# schaltplan_v2.net
KiCad netlist of a schematic drawn in EAGLE
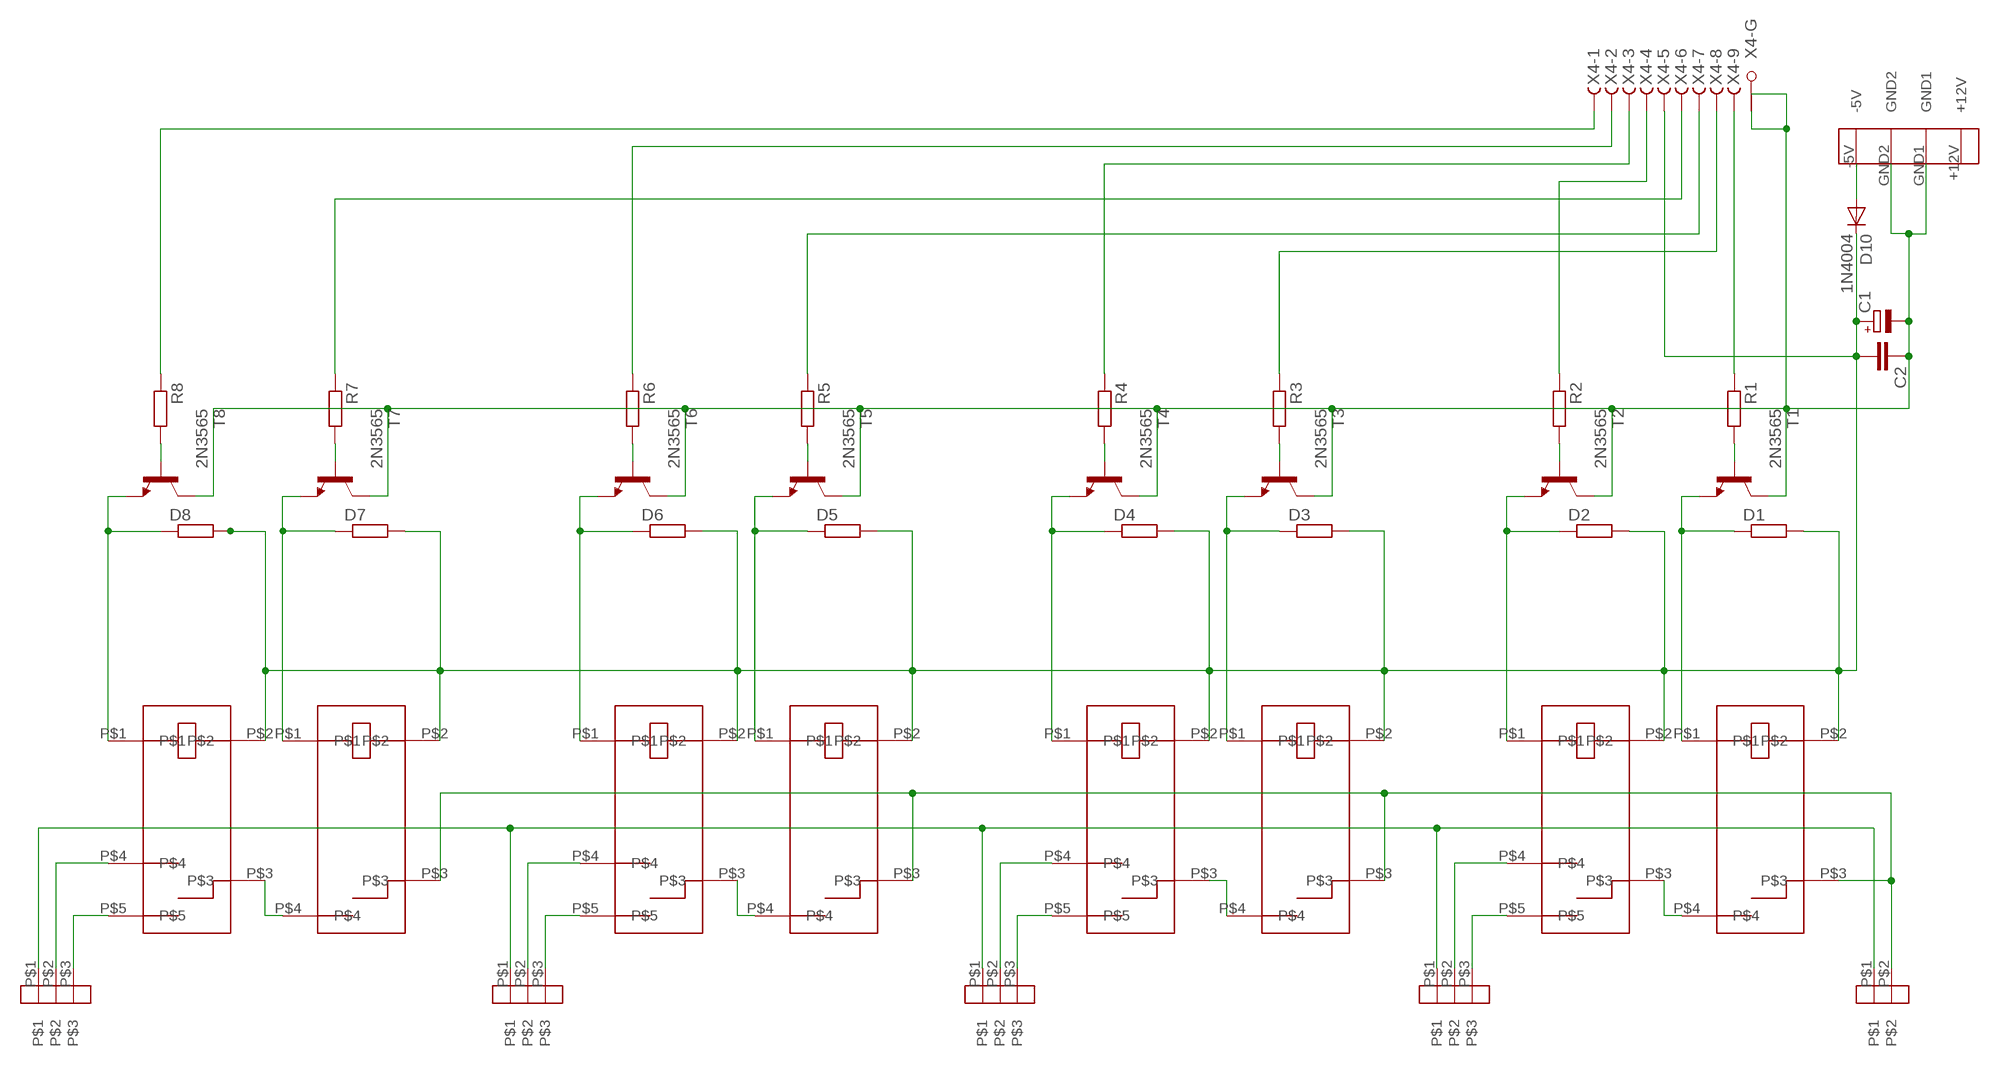
[diagram p0: schematic, sheet 1]

(export (version "E")
  (design (tool "Eeschema 10.0.6"))
  (components
    (comp (ref "C1")
      (value "CPOL-EUE3.5-8")
      (footprint "eagle-import:E3,5-8")
      (libsource (lib "eagle-import") (part "CPOL-EUE3.5-8"))
    )
    (comp (ref "C2")
      (value "C-EU025-030X050")
      (footprint "eagle-import:C025-030X050")
      (libsource (lib "eagle-import") (part "C-EU025-030X050"))
    )
    (comp (ref "D1")
      (value "R-EU_0207/2V")
      (footprint "eagle-import:0207_2V")
      (libsource (lib "eagle-import") (part "R-EU_0207/2V"))
    )
    (comp (ref "D2")
      (value "R-EU_0207/2V")
      (footprint "eagle-import:0207_2V")
      (libsource (lib "eagle-import") (part "R-EU_0207/2V"))
    )
    (comp (ref "D3")
      (value "R-EU_0207/2V")
      (footprint "eagle-import:0207_2V")
      (libsource (lib "eagle-import") (part "R-EU_0207/2V"))
    )
    (comp (ref "D4")
      (value "R-EU_0207/2V")
      (footprint "eagle-import:0207_2V")
      (libsource (lib "eagle-import") (part "R-EU_0207/2V"))
    )
    (comp (ref "D5")
      (value "R-EU_0207/2V")
      (footprint "eagle-import:0207_2V")
      (libsource (lib "eagle-import") (part "R-EU_0207/2V"))
    )
    (comp (ref "D6")
      (value "R-EU_0207/2V")
      (footprint "eagle-import:0207_2V")
      (libsource (lib "eagle-import") (part "R-EU_0207/2V"))
    )
    (comp (ref "D7")
      (value "R-EU_0207/2V")
      (footprint "eagle-import:0207_2V")
      (libsource (lib "eagle-import") (part "R-EU_0207/2V"))
    )
    (comp (ref "D8")
      (value "R-EU_0207/2V")
      (footprint "eagle-import:0207_2V")
      (libsource (lib "eagle-import") (part "R-EU_0207/2V"))
    )
    (comp (ref "D10")
      (value "1N4004")
      (footprint "eagle-import:DO41-10")
      (libsource (lib "eagle-import") (part "1N4004"))
    )
    (comp (ref "R1")
      (value "R-EU_0207/7")
      (footprint "eagle-import:0207_7")
      (libsource (lib "eagle-import") (part "R-EU_0207/7"))
    )
    (comp (ref "R2")
      (value "R-EU_0207/7")
      (footprint "eagle-import:0207_7")
      (libsource (lib "eagle-import") (part "R-EU_0207/7"))
    )
    (comp (ref "R3")
      (value "R-EU_0207/7")
      (footprint "eagle-import:0207_7")
      (libsource (lib "eagle-import") (part "R-EU_0207/7"))
    )
    (comp (ref "R4")
      (value "R-EU_0207/7")
      (footprint "eagle-import:0207_7")
      (libsource (lib "eagle-import") (part "R-EU_0207/7"))
    )
    (comp (ref "R5")
      (value "R-EU_0207/7")
      (footprint "eagle-import:0207_7")
      (libsource (lib "eagle-import") (part "R-EU_0207/7"))
    )
    (comp (ref "R6")
      (value "R-EU_0207/7")
      (footprint "eagle-import:0207_7")
      (libsource (lib "eagle-import") (part "R-EU_0207/7"))
    )
    (comp (ref "R7")
      (value "R-EU_0207/7")
      (footprint "eagle-import:0207_7")
      (libsource (lib "eagle-import") (part "R-EU_0207/7"))
    )
    (comp (ref "R8")
      (value "R-EU_0207/7")
      (footprint "eagle-import:0207_7")
      (libsource (lib "eagle-import") (part "R-EU_0207/7"))
    )
    (comp (ref "T1")
      (value "2N3565")
      (footprint "eagle-import:TO92")
      (libsource (lib "eagle-import") (part "2N3565"))
    )
    (comp (ref "T2")
      (value "2N3565")
      (footprint "eagle-import:TO92")
      (libsource (lib "eagle-import") (part "2N3565"))
    )
    (comp (ref "T3")
      (value "2N3565")
      (footprint "eagle-import:TO92")
      (libsource (lib "eagle-import") (part "2N3565"))
    )
    (comp (ref "T4")
      (value "2N3565")
      (footprint "eagle-import:TO92")
      (libsource (lib "eagle-import") (part "2N3565"))
    )
    (comp (ref "T5")
      (value "2N3565")
      (footprint "eagle-import:TO92")
      (libsource (lib "eagle-import") (part "2N3565"))
    )
    (comp (ref "T6")
      (value "2N3565")
      (footprint "eagle-import:TO92")
      (libsource (lib "eagle-import") (part "2N3565"))
    )
    (comp (ref "T7")
      (value "2N3565")
      (footprint "eagle-import:TO92")
      (libsource (lib "eagle-import") (part "2N3565"))
    )
    (comp (ref "T8")
      (value "2N3565")
      (footprint "eagle-import:TO92")
      (libsource (lib "eagle-import") (part "2N3565"))
    )
    (comp (ref "U$1")
      (value "JS_05_MN_KT")
      (footprint "eagle-import:JS_05_MN_KT")
      (libsource (lib "eagle-import") (part "JS_05_MN_KT"))
    )
    (comp (ref "U$2")
      (value "JS_05_N_K")
      (footprint "eagle-import:JS_05_N_K")
      (libsource (lib "eagle-import") (part "JS_05_N_K"))
    )
    (comp (ref "U$3")
      (value "JS_05_MN_KT")
      (footprint "eagle-import:JS_05_MN_KT")
      (libsource (lib "eagle-import") (part "JS_05_MN_KT"))
    )
    (comp (ref "U$4")
      (value "JS_05_N_K")
      (footprint "eagle-import:JS_05_N_K")
      (libsource (lib "eagle-import") (part "JS_05_N_K"))
    )
    (comp (ref "U$5")
      (value "JS_05_MN_KT")
      (footprint "eagle-import:JS_05_MN_KT")
      (libsource (lib "eagle-import") (part "JS_05_MN_KT"))
    )
    (comp (ref "U$6")
      (value "JS_05_N_K")
      (footprint "eagle-import:JS_05_N_K")
      (libsource (lib "eagle-import") (part "JS_05_N_K"))
    )
    (comp (ref "U$7")
      (value "JS_05_MN_KT")
      (footprint "eagle-import:JS_05_MN_KT")
      (libsource (lib "eagle-import") (part "JS_05_MN_KT"))
    )
    (comp (ref "U$8")
      (value "JS_05_N_K")
      (footprint "eagle-import:JS_05_N_K")
      (libsource (lib "eagle-import") (part "JS_05_N_K"))
    )
    (comp (ref "U$9")
      (value "WAGO_734_262")
      (footprint "eagle-import:WAGO_734_262")
      (libsource (lib "eagle-import") (part "WAGO_734_262"))
    )
    (comp (ref "U$10")
      (value "WAGO_734_263")
      (footprint "eagle-import:WAGO_734_263")
      (libsource (lib "eagle-import") (part "WAGO_734_263"))
    )
    (comp (ref "U$11")
      (value "WAGO_734_263")
      (footprint "eagle-import:WAGO_734_263")
      (libsource (lib "eagle-import") (part "WAGO_734_263"))
    )
    (comp (ref "U$12")
      (value "WAGO_734_263")
      (footprint "eagle-import:WAGO_734_263")
      (libsource (lib "eagle-import") (part "WAGO_734_263"))
    )
    (comp (ref "U$13")
      (value "WAGO_734_263")
      (footprint "eagle-import:WAGO_734_263")
      (libsource (lib "eagle-import") (part "WAGO_734_263"))
    )
    (comp (ref "U$14")
      (value "PSW_5")
      (footprint "eagle-import:PSW_5")
      (libsource (lib "eagle-import") (part "PSW_5"))
    )
    (comp (ref "X4")
      (value "F09HPS")
      (footprint "eagle-import:F09HP")
      (libsource (lib "eagle-import") (part "F09HPS"))
    )
  )
  (nets
    (net (code "1") (name "Net-(D10-PadA)") (class "Default")
      (node (ref "D10") (pin "A") (pinfunction "A_A") (pintype "passive"))
      (node (ref "U$14") (pin "-5V") (pinfunction "-5V_-5V") (pintype "bidirectional"))
    )
    (net (code "2") (name "Net-(T1-B)") (class "Default")
      (node (ref "R1") (pin "2") (pinfunction "2_2") (pintype "passive"))
      (node (ref "T1") (pin "2") (pinfunction "B_2") (pintype "passive"))
    )
    (net (code "3") (name "Net-(T1-C)") (class "Default")
      (node (ref "C1") (pin "-") (pinfunction "-_-") (pintype "passive"))
      (node (ref "C2") (pin "1") (pinfunction "1_1") (pintype "passive"))
      (node (ref "T1") (pin "1") (pinfunction "C_1") (pintype "passive"))
      (node (ref "T2") (pin "1") (pinfunction "C_1") (pintype "passive"))
      (node (ref "T3") (pin "1") (pinfunction "C_1") (pintype "passive"))
      (node (ref "T4") (pin "1") (pinfunction "C_1") (pintype "passive"))
      (node (ref "T5") (pin "1") (pinfunction "C_1") (pintype "passive"))
      (node (ref "T6") (pin "1") (pinfunction "C_1") (pintype "passive"))
      (node (ref "T7") (pin "1") (pinfunction "C_1") (pintype "passive"))
      (node (ref "T8") (pin "1") (pinfunction "C_1") (pintype "passive"))
      (node (ref "U$14") (pin "GND1") (pinfunction "GND1_GND1") (pintype "bidirectional"))
      (node (ref "U$14") (pin "GND2") (pinfunction "GND2_GND2") (pintype "bidirectional"))
      (node (ref "X4") (pin "G1") (pinfunction "G1_G1") (pintype "passive"))
      (node (ref "X4") (pin "G2") (pinfunction "G2_G2") (pintype "passive"))
    )
    (net (code "4") (name "Net-(T1-E)") (class "Default")
      (node (ref "D1") (pin "1") (pinfunction "1_1") (pintype "passive"))
      (node (ref "T1") (pin "3") (pinfunction "E_3") (pintype "passive"))
      (node (ref "U$1") (pin "P$1") (pinfunction "P$1_P$1") (pintype "bidirectional"))
    )
    (net (code "5") (name "Net-(T2-B)") (class "Default")
      (node (ref "R2") (pin "2") (pinfunction "2_2") (pintype "passive"))
      (node (ref "T2") (pin "2") (pinfunction "B_2") (pintype "passive"))
    )
    (net (code "6") (name "Net-(T2-E)") (class "Default")
      (node (ref "D2") (pin "1") (pinfunction "1_1") (pintype "passive"))
      (node (ref "T2") (pin "3") (pinfunction "E_3") (pintype "passive"))
      (node (ref "U$2") (pin "P$1") (pinfunction "P$1_P$1") (pintype "bidirectional"))
    )
    (net (code "7") (name "Net-(T3-B)") (class "Default")
      (node (ref "R3") (pin "2") (pinfunction "2_2") (pintype "passive"))
      (node (ref "T3") (pin "2") (pinfunction "B_2") (pintype "passive"))
    )
    (net (code "8") (name "Net-(T3-E)") (class "Default")
      (node (ref "D3") (pin "1") (pinfunction "1_1") (pintype "passive"))
      (node (ref "T3") (pin "3") (pinfunction "E_3") (pintype "passive"))
      (node (ref "U$3") (pin "P$1") (pinfunction "P$1_P$1") (pintype "bidirectional"))
    )
    (net (code "9") (name "Net-(T4-B)") (class "Default")
      (node (ref "R4") (pin "2") (pinfunction "2_2") (pintype "passive"))
      (node (ref "T4") (pin "2") (pinfunction "B_2") (pintype "passive"))
    )
    (net (code "10") (name "Net-(T4-E)") (class "Default")
      (node (ref "D4") (pin "1") (pinfunction "1_1") (pintype "passive"))
      (node (ref "T4") (pin "3") (pinfunction "E_3") (pintype "passive"))
      (node (ref "U$4") (pin "P$1") (pinfunction "P$1_P$1") (pintype "bidirectional"))
    )
    (net (code "11") (name "Net-(T5-B)") (class "Default")
      (node (ref "R5") (pin "2") (pinfunction "2_2") (pintype "passive"))
      (node (ref "T5") (pin "2") (pinfunction "B_2") (pintype "passive"))
    )
    (net (code "12") (name "Net-(T5-E)") (class "Default")
      (node (ref "D5") (pin "1") (pinfunction "1_1") (pintype "passive"))
      (node (ref "T5") (pin "3") (pinfunction "E_3") (pintype "passive"))
      (node (ref "U$5") (pin "P$1") (pinfunction "P$1_P$1") (pintype "bidirectional"))
    )
    (net (code "13") (name "Net-(T6-B)") (class "Default")
      (node (ref "R6") (pin "2") (pinfunction "2_2") (pintype "passive"))
      (node (ref "T6") (pin "2") (pinfunction "B_2") (pintype "passive"))
    )
    (net (code "14") (name "Net-(T6-E)") (class "Default")
      (node (ref "D6") (pin "1") (pinfunction "1_1") (pintype "passive"))
      (node (ref "T6") (pin "3") (pinfunction "E_3") (pintype "passive"))
      (node (ref "U$6") (pin "P$1") (pinfunction "P$1_P$1") (pintype "bidirectional"))
    )
    (net (code "15") (name "Net-(T7-B)") (class "Default")
      (node (ref "R7") (pin "2") (pinfunction "2_2") (pintype "passive"))
      (node (ref "T7") (pin "2") (pinfunction "B_2") (pintype "passive"))
    )
    (net (code "16") (name "Net-(T7-E)") (class "Default")
      (node (ref "D7") (pin "1") (pinfunction "1_1") (pintype "passive"))
      (node (ref "T7") (pin "3") (pinfunction "E_3") (pintype "passive"))
      (node (ref "U$7") (pin "P$1") (pinfunction "P$1_P$1") (pintype "bidirectional"))
    )
    (net (code "17") (name "Net-(T8-B)") (class "Default")
      (node (ref "R8") (pin "2") (pinfunction "2_2") (pintype "passive"))
      (node (ref "T8") (pin "2") (pinfunction "B_2") (pintype "passive"))
    )
    (net (code "18") (name "Net-(T8-E)") (class "Default")
      (node (ref "D8") (pin "1") (pinfunction "1_1") (pintype "passive"))
      (node (ref "T8") (pin "3") (pinfunction "E_3") (pintype "passive"))
      (node (ref "U$8") (pin "P$1") (pinfunction "P$1_P$1") (pintype "bidirectional"))
    )
    (net (code "19") (name "Net-(U$1-PadP$3)") (class "Default")
      (node (ref "U$1") (pin "P$3") (pinfunction "P$3_P$3") (pintype "bidirectional"))
      (node (ref "U$3") (pin "P$3") (pinfunction "P$3_P$3") (pintype "bidirectional"))
      (node (ref "U$5") (pin "P$3") (pinfunction "P$3_P$3") (pintype "bidirectional"))
      (node (ref "U$7") (pin "P$3") (pinfunction "P$3_P$3") (pintype "bidirectional"))
      (node (ref "U$9") (pin "P$2") (pinfunction "P$2_P$2") (pintype "bidirectional"))
    )
    (net (code "20") (name "Net-(U$1-PadP$4)") (class "Default")
      (node (ref "U$1") (pin "P$4") (pinfunction "P$4_P$4") (pintype "bidirectional"))
      (node (ref "U$2") (pin "P$3") (pinfunction "P$3_P$3") (pintype "bidirectional"))
    )
    (net (code "21") (name "Net-(U$3-PadP$4)") (class "Default")
      (node (ref "U$3") (pin "P$4") (pinfunction "P$4_P$4") (pintype "bidirectional"))
      (node (ref "U$4") (pin "P$3") (pinfunction "P$3_P$3") (pintype "bidirectional"))
    )
    (net (code "22") (name "Net-(U$5-PadP$4)") (class "Default")
      (node (ref "U$5") (pin "P$4") (pinfunction "P$4_P$4") (pintype "bidirectional"))
      (node (ref "U$6") (pin "P$3") (pinfunction "P$3_P$3") (pintype "bidirectional"))
    )
    (net (code "23") (name "Net-(U$7-PadP$4)") (class "Default")
      (node (ref "U$7") (pin "P$4") (pinfunction "P$4_P$4") (pintype "bidirectional"))
      (node (ref "U$8") (pin "P$3") (pinfunction "P$3_P$3") (pintype "bidirectional"))
    )
    (net (code "24") (name "Net-(U$10-PadP$1)") (class "Default")
      (node (ref "U$10") (pin "P$1") (pinfunction "P$1_P$1") (pintype "bidirectional"))
      (node (ref "U$11") (pin "P$1") (pinfunction "P$1_P$1") (pintype "bidirectional"))
      (node (ref "U$12") (pin "P$1") (pinfunction "P$1_P$1") (pintype "bidirectional"))
      (node (ref "U$13") (pin "P$1") (pinfunction "P$1_P$1") (pintype "bidirectional"))
      (node (ref "U$9") (pin "P$1") (pinfunction "P$1_P$1") (pintype "bidirectional"))
    )
    (net (code "25") (name "Net-(U$10-PadP$2)") (class "Default")
      (node (ref "U$10") (pin "P$2") (pinfunction "P$2_P$2") (pintype "bidirectional"))
      (node (ref "U$2") (pin "P$4") (pinfunction "P$4_P$4") (pintype "bidirectional"))
    )
    (net (code "26") (name "Net-(U$10-PadP$3)") (class "Default")
      (node (ref "U$10") (pin "P$3") (pinfunction "P$3_P$3") (pintype "bidirectional"))
      (node (ref "U$2") (pin "P$5") (pinfunction "P$5_P$5") (pintype "bidirectional"))
    )
    (net (code "27") (name "Net-(U$11-PadP$2)") (class "Default")
      (node (ref "U$11") (pin "P$2") (pinfunction "P$2_P$2") (pintype "bidirectional"))
      (node (ref "U$4") (pin "P$4") (pinfunction "P$4_P$4") (pintype "bidirectional"))
    )
    (net (code "28") (name "Net-(U$11-PadP$3)") (class "Default")
      (node (ref "U$11") (pin "P$3") (pinfunction "P$3_P$3") (pintype "bidirectional"))
      (node (ref "U$4") (pin "P$5") (pinfunction "P$5_P$5") (pintype "bidirectional"))
    )
    (net (code "29") (name "Net-(U$12-PadP$2)") (class "Default")
      (node (ref "U$12") (pin "P$2") (pinfunction "P$2_P$2") (pintype "bidirectional"))
      (node (ref "U$6") (pin "P$4") (pinfunction "P$4_P$4") (pintype "bidirectional"))
    )
    (net (code "30") (name "Net-(U$12-PadP$3)") (class "Default")
      (node (ref "U$12") (pin "P$3") (pinfunction "P$3_P$3") (pintype "bidirectional"))
      (node (ref "U$6") (pin "P$5") (pinfunction "P$5_P$5") (pintype "bidirectional"))
    )
    (net (code "31") (name "Net-(U$13-PadP$2)") (class "Default")
      (node (ref "U$13") (pin "P$2") (pinfunction "P$2_P$2") (pintype "bidirectional"))
      (node (ref "U$8") (pin "P$4") (pinfunction "P$4_P$4") (pintype "bidirectional"))
    )
    (net (code "32") (name "Net-(U$13-PadP$3)") (class "Default")
      (node (ref "U$13") (pin "P$3") (pinfunction "P$3_P$3") (pintype "bidirectional"))
      (node (ref "U$8") (pin "P$5") (pinfunction "P$5_P$5") (pintype "bidirectional"))
    )
    (net (code "33") (name "Net-(X4A-F)") (class "Default")
      (node (ref "R8") (pin "1") (pinfunction "1_1") (pintype "passive"))
      (node (ref "X4") (pin "1") (pinfunction "F_1") (pintype "passive"))
    )
    (net (code "34") (name "Net-(X4B-F)") (class "Default")
      (node (ref "R6") (pin "1") (pinfunction "1_1") (pintype "passive"))
      (node (ref "X4") (pin "2") (pinfunction "F_2") (pintype "passive"))
    )
    (net (code "35") (name "Net-(X4C-F)") (class "Default")
      (node (ref "R4") (pin "1") (pinfunction "1_1") (pintype "passive"))
      (node (ref "X4") (pin "3") (pinfunction "F_3") (pintype "passive"))
    )
    (net (code "36") (name "Net-(X4D-F)") (class "Default")
      (node (ref "R2") (pin "1") (pinfunction "1_1") (pintype "passive"))
      (node (ref "X4") (pin "4") (pinfunction "F_4") (pintype "passive"))
    )
    (net (code "37") (name "Net-(X4E-F)") (class "Default")
      (node (ref "C1") (pin "+") (pinfunction "+_+") (pintype "passive"))
      (node (ref "C2") (pin "2") (pinfunction "2_2") (pintype "passive"))
      (node (ref "D1") (pin "2") (pinfunction "2_2") (pintype "passive"))
      (node (ref "D10") (pin "C") (pinfunction "C_C") (pintype "passive"))
      (node (ref "D2") (pin "2") (pinfunction "2_2") (pintype "passive"))
      (node (ref "D3") (pin "2") (pinfunction "2_2") (pintype "passive"))
      (node (ref "D4") (pin "2") (pinfunction "2_2") (pintype "passive"))
      (node (ref "D5") (pin "2") (pinfunction "2_2") (pintype "passive"))
      (node (ref "D6") (pin "2") (pinfunction "2_2") (pintype "passive"))
      (node (ref "D7") (pin "2") (pinfunction "2_2") (pintype "passive"))
      (node (ref "D8") (pin "2") (pinfunction "2_2") (pintype "passive"))
      (node (ref "U$1") (pin "P$2") (pinfunction "P$2_P$2") (pintype "bidirectional"))
      (node (ref "U$2") (pin "P$2") (pinfunction "P$2_P$2") (pintype "bidirectional"))
      (node (ref "U$3") (pin "P$2") (pinfunction "P$2_P$2") (pintype "bidirectional"))
      (node (ref "U$4") (pin "P$2") (pinfunction "P$2_P$2") (pintype "bidirectional"))
      (node (ref "U$5") (pin "P$2") (pinfunction "P$2_P$2") (pintype "bidirectional"))
      (node (ref "U$6") (pin "P$2") (pinfunction "P$2_P$2") (pintype "bidirectional"))
      (node (ref "U$7") (pin "P$2") (pinfunction "P$2_P$2") (pintype "bidirectional"))
      (node (ref "U$8") (pin "P$2") (pinfunction "P$2_P$2") (pintype "bidirectional"))
      (node (ref "X4") (pin "5") (pinfunction "F_5") (pintype "passive"))
    )
    (net (code "38") (name "Net-(X4F-F)") (class "Default")
      (node (ref "R7") (pin "1") (pinfunction "1_1") (pintype "passive"))
      (node (ref "X4") (pin "6") (pinfunction "F_6") (pintype "passive"))
    )
    (net (code "39") (name "Net-(X4G-F)") (class "Default")
      (node (ref "R5") (pin "1") (pinfunction "1_1") (pintype "passive"))
      (node (ref "X4") (pin "7") (pinfunction "F_7") (pintype "passive"))
    )
    (net (code "40") (name "Net-(X4H-F)") (class "Default")
      (node (ref "R3") (pin "1") (pinfunction "1_1") (pintype "passive"))
      (node (ref "X4") (pin "8") (pinfunction "F_8") (pintype "passive"))
    )
    (net (code "41") (name "Net-(X4I-F)") (class "Default")
      (node (ref "R1") (pin "1") (pinfunction "1_1") (pintype "passive"))
      (node (ref "X4") (pin "9") (pinfunction "F_9") (pintype "passive"))
    )
    (net (code "42") (name "unconnected-(U$14-Pad+12V)") (class "Default")
      (node (ref "U$14") (pin "+12V") (pinfunction "+12V_+12V") (pintype "bidirectional"))
    )
  )
)
